# Cube_Motherboard.net
KiCad netlist of a schematic drawn in Altium Designer
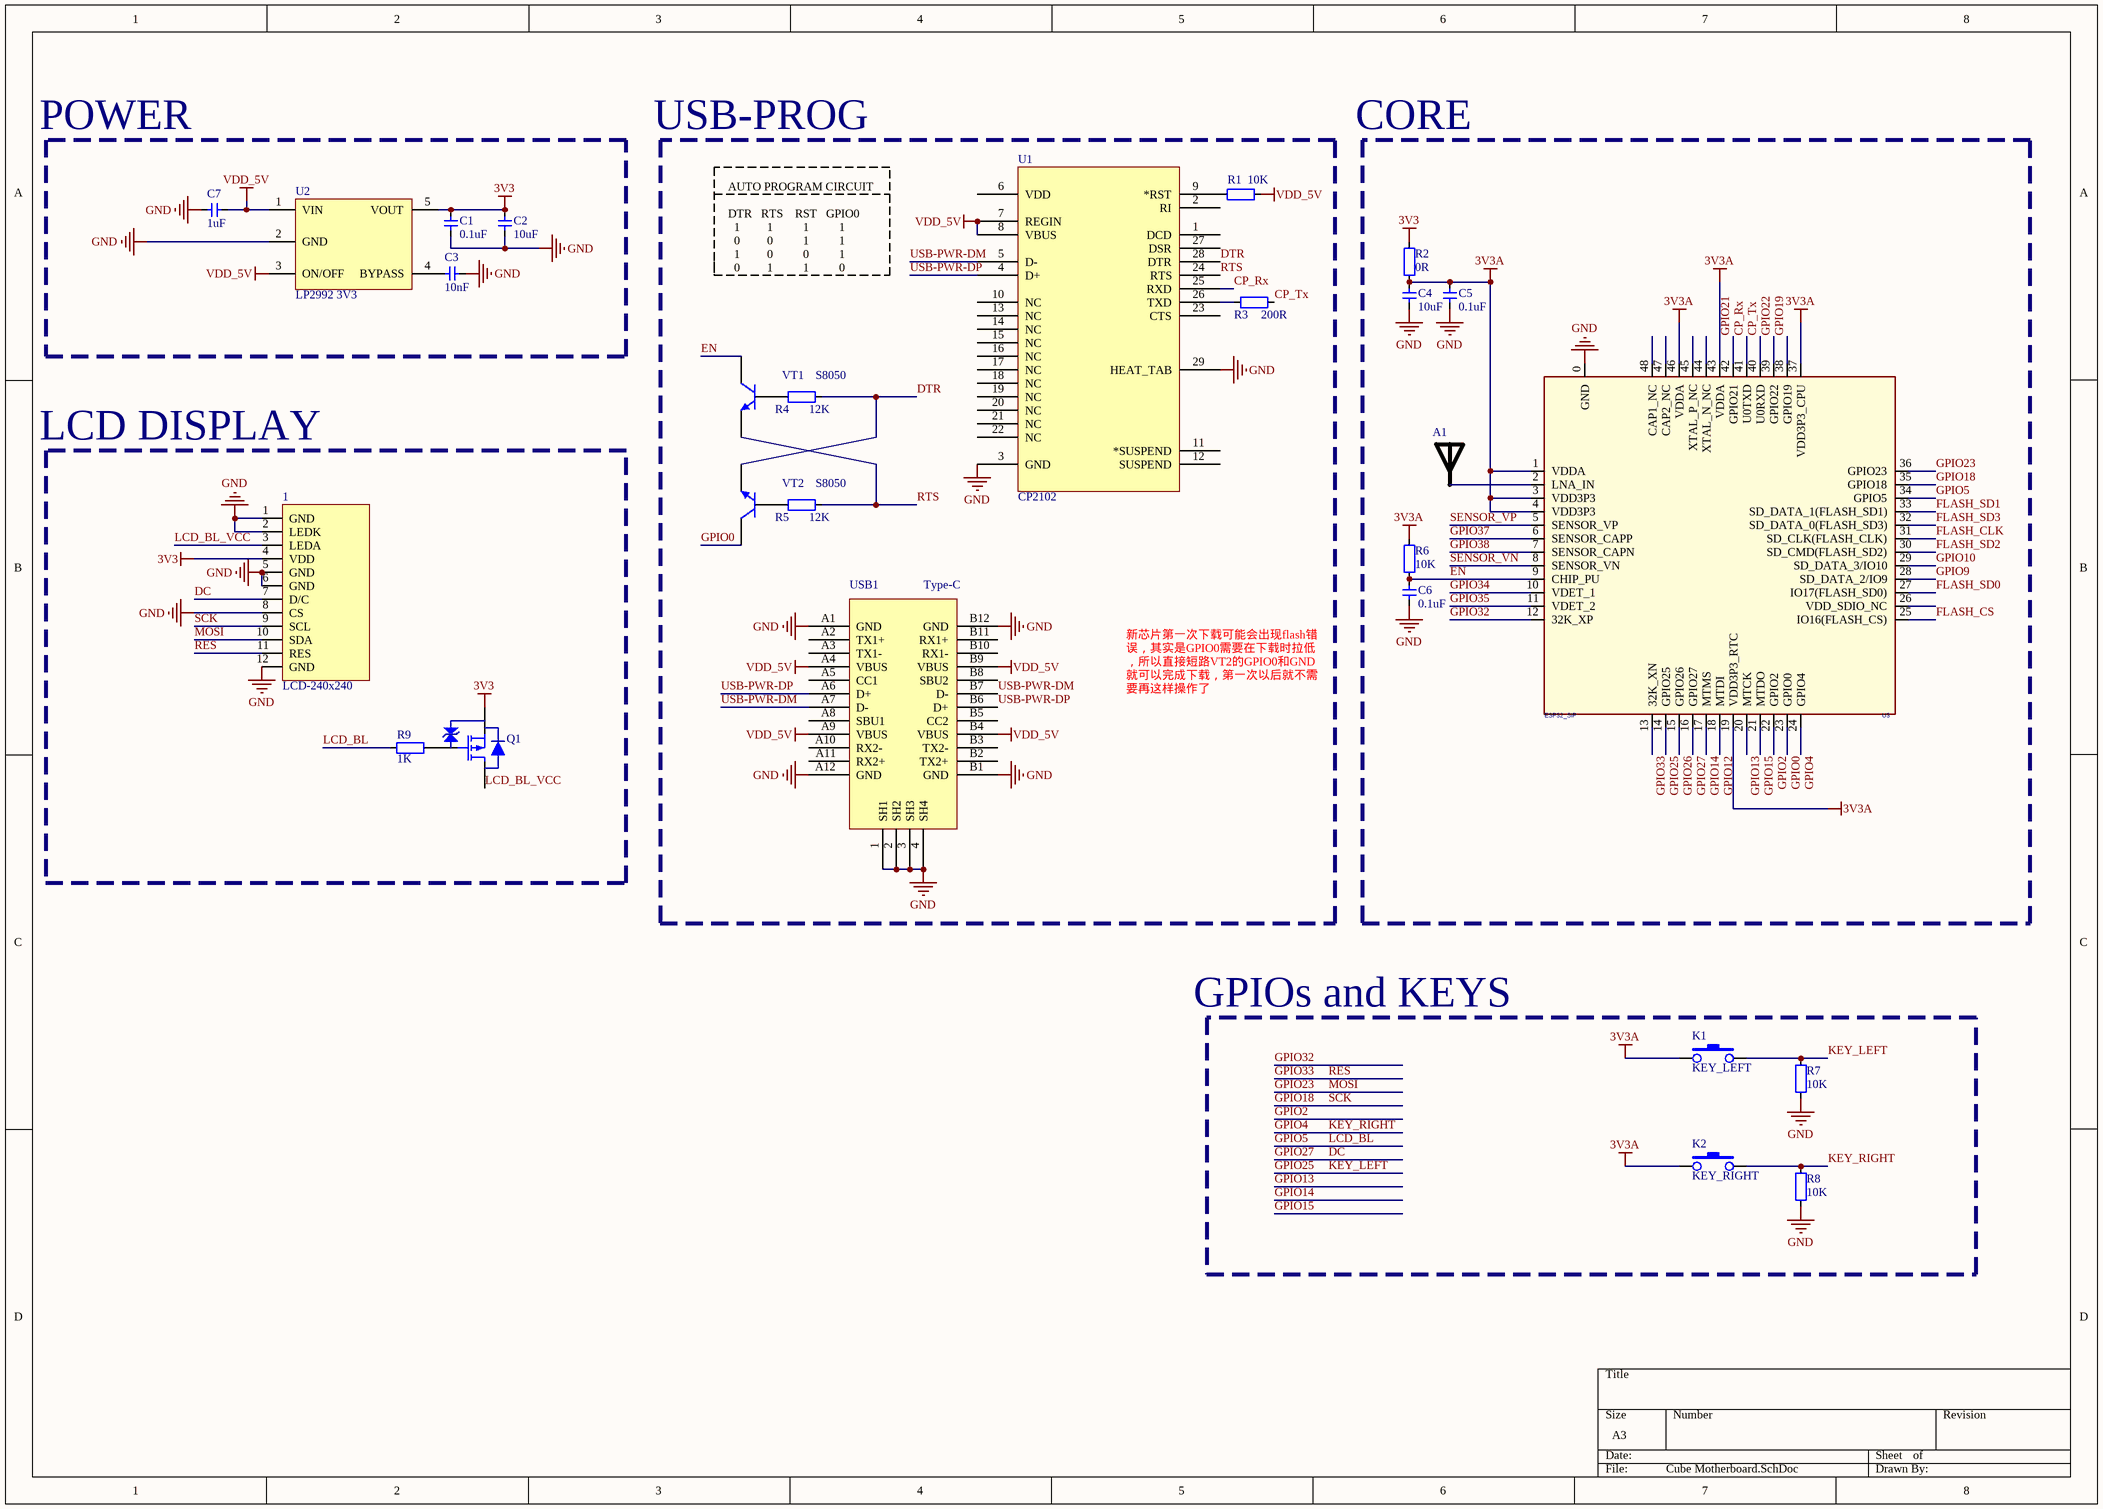
[diagram p0: Cube Motherboard.SchDoc]

(export (version "E")
  (design (tool "Eeschema 10.0.6"))
  (components
    (comp (ref "1")
      (value "LCD-240x240")
      (footprint "LCD-240X240-NOHOLE")
      (description "显示屏")
      (libsource (lib "mLib") (part "LCD-240x240"))
    )
    (comp (ref "A1")
      (value "RAINSUN")
      (footprint "ANT-Rainsun-AN5120")
      (libsource (lib "MyPcbLib") (part "ANT-Rainsun-AP5120"))
    )
    (comp (ref "C1")
      (value "0.1uF")
      (footprint "0603C")
      (description "Capacitor")
      (libsource (lib "MyPcbLib") (part "电容-0402"))
    )
    (comp (ref "C2")
      (value "10uF")
      (footprint "0603C")
      (description "Capacitor")
      (libsource (lib "MyPcbLib") (part "电容-0402"))
    )
    (comp (ref "C3")
      (value "10nF")
      (footprint "0603C")
      (description "Capacitor")
      (libsource (lib "MyPcbLib") (part "电容-0402"))
    )
    (comp (ref "C4")
      (value "10uF")
      (footprint "0603C")
      (description "Capacitor")
      (libsource (lib "MyPcbLib") (part "电容-0402"))
    )
    (comp (ref "C5")
      (value "0.1uF")
      (footprint "0603C")
      (description "Capacitor")
      (libsource (lib "MyPcbLib") (part "电容-0402"))
    )
    (comp (ref "C6")
      (value "0.1uF")
      (footprint "0603C")
      (description "Capacitor")
      (libsource (lib "MyPcbLib") (part "电容-0402"))
    )
    (comp (ref "C7")
      (value "1uF")
      (footprint "0603C")
      (description "Capacitor")
      (libsource (lib "MyPcbLib") (part "电容-0402"))
    )
    (comp (ref "K1") (value "KEY_LEFT") (footprint "SMD-SW2X4") (libsource (lib "轻触开关") (part "KEY")))
    (comp (ref "K2") (value "KEY_RIGHT") (footprint "SMD-SW2X4") (libsource (lib "轻触开关") (part "KEY")))
    (comp (ref "Q1")
      (value "AO3415A")
      (footprint "SOT23-3")
      (description "MOSFET")
      (fields (field (name "PUBLISHER") "Altium Limited"))
      (libsource (lib "MyPcbLib") (part "AO3415A"))
    )
    (comp (ref "R1")
      (value "10K")
      (footprint "0603R")
      (description "Resistor")
      (libsource (lib "") (part "电阻-0402_1"))
    )
    (comp (ref "R2")
      (value "0R")
      (footprint "0603R")
      (description "Resistor")
      (libsource (lib "MyPcbLib") (part "电阻-0402"))
    )
    (comp (ref "R3")
      (value "200R")
      (footprint "0603R")
      (description "Resistor")
      (libsource (lib "") (part "电阻-0402_1"))
    )
    (comp (ref "R4")
      (value "12K")
      (footprint "0603R")
      (description "Resistor")
      (libsource (lib "") (part "电阻-0402_1"))
    )
    (comp (ref "R5")
      (value "12K")
      (footprint "0603R")
      (description "Resistor")
      (libsource (lib "") (part "电阻-0402_1"))
    )
    (comp (ref "R6")
      (value "10K")
      (footprint "0603R")
      (description "Resistor")
      (libsource (lib "MyPcbLib") (part "电阻-0402"))
    )
    (comp (ref "R7")
      (value "10K")
      (footprint "0603R")
      (description "Resistor")
      (libsource (lib "MyPcbLib") (part "电阻-0402"))
    )
    (comp (ref "R8")
      (value "10K")
      (footprint "0603R")
      (description "Resistor")
      (libsource (lib "MyPcbLib") (part "电阻-0402"))
    )
    (comp (ref "R9")
      (value "1K")
      (footprint "0603R")
      (description "Resistor")
      (libsource (lib "") (part "电阻-0402_2"))
    )
    (comp (ref "U1")
      (value "CP2102")
      (footprint "QFN-28")
      (description "USB转TTL")
      (libsource (lib "mLib") (part "CP2102"))
    )
    (comp (ref "U2")
      (value "LP2992 3V3")
      (footprint "SOT23-5")
      (description "LDO")
      (libsource (lib "MyPcbLib") (part "LP2992"))
    )
    (comp (ref "U3")
      (value "ESP32_SIP")
      (footprint "QFN-48_7X7")
      (libsource (lib "MyPcbLib") (part "ESP32-PICO"))
    )
    (comp (ref "USB1")
      (value "Type-C")
      (footprint "Type-C-TOP")
      (libsource (lib "MyPcbLib") (part "USB-Type-C-TOP"))
    )
    (comp (ref "VT1")
      (value "S8050")
      (footprint "SMT_TRIODE_NPN")
      (description "Surface mount NPN transistor, package SOT-23")
      (libsource (lib "MyPcbLib") (part "SMT_TRIODE_NPN"))
    )
    (comp (ref "VT2")
      (value "S8050")
      (footprint "SMT_TRIODE_NPN")
      (description "Surface mount NPN transistor, package SOT-23")
      (libsource (lib "MyPcbLib") (part "SMT_TRIODE_NPN"))
    )
  )
  (nets
    (net (code "1") (name "/CP_Rx") (class "Default")
      (node (ref "U1") (pin "25") (pinfunction "RXD_25") (pintype "passive"))
      (node (ref "U3") (pin "41") (pinfunction "U0TXD_41") (pintype "power_in"))
    )
    (net (code "2") (name "/CP_Tx") (class "Default")
      (node (ref "R3") (pin "1") (pinfunction "1_1") (pintype "passive"))
      (node (ref "U3") (pin "40") (pinfunction "U0RXD_40") (pintype "power_in"))
    )
    (net (code "3") (name "/DC") (class "Default")
      (node (ref "1") (pin "7") (pinfunction "D/C_7") (pintype "passive"))
      (node (ref "U3") (pin "16") (pinfunction "GPIO27_16") (pintype "passive"))
    )
    (net (code "4") (name "/DTR") (class "Default")
      (node (ref "R4") (pin "1") (pinfunction "1_1") (pintype "passive"))
      (node (ref "U1") (pin "28") (pinfunction "DTR_28") (pintype "passive"))
      (node (ref "VT2") (pin "2") (pinfunction "E_2") (pintype "passive"))
    )
    (net (code "5") (name "/EN") (class "Default")
      (node (ref "C6") (pin "1") (pinfunction "1_1") (pintype "passive"))
      (node (ref "R6") (pin "2") (pinfunction "2_2") (pintype "passive"))
      (node (ref "U3") (pin "9") (pinfunction "CHIP_PU_9") (pintype "passive"))
      (node (ref "VT1") (pin "3") (pinfunction "C_3") (pintype "passive"))
    )
    (net (code "6") (name "/FLASH_CLK") (class "Default")
      (node (ref "U3") (pin "31") (pinfunction "SD_CLK(FLASH_CLK)_31") (pintype "passive"))
    )
    (net (code "7") (name "/FLASH_CS") (class "Default")
      (node (ref "U3") (pin "25") (pinfunction "IO16(FLASH_CS)_25") (pintype "passive"))
    )
    (net (code "8") (name "/FLASH_SD0") (class "Default")
      (node (ref "U3") (pin "27") (pinfunction "IO17(FLASH_SD0)_27") (pintype "passive"))
    )
    (net (code "9") (name "/FLASH_SD1") (class "Default")
      (node (ref "U3") (pin "33") (pinfunction "SD_DATA_1(FLASH_SD1)_33") (pintype "passive"))
    )
    (net (code "10") (name "/FLASH_SD2") (class "Default")
      (node (ref "U3") (pin "30") (pinfunction "SD_CMD(FLASH_SD2)_30") (pintype "passive"))
    )
    (net (code "11") (name "/FLASH_SD3") (class "Default")
      (node (ref "U3") (pin "32") (pinfunction "SD_DATA_0(FLASH_SD3)_32") (pintype "passive"))
    )
    (net (code "12") (name "/GPIO0") (class "Default")
      (node (ref "U3") (pin "23") (pinfunction "GPIO0_23") (pintype "passive"))
      (node (ref "VT2") (pin "3") (pinfunction "C_3") (pintype "passive"))
    )
    (net (code "13") (name "/GPIO2") (class "Default")
      (node (ref "U3") (pin "22") (pinfunction "GPIO2_22") (pintype "passive"))
    )
    (net (code "14") (name "/GPIO4") (class "Default")
      (node (ref "K2") (pin "3") (pinfunction "3_3") (pintype "passive"))
      (node (ref "R8") (pin "1") (pinfunction "1_1") (pintype "passive"))
      (node (ref "U3") (pin "24") (pinfunction "GPIO4_24") (pintype "passive"))
    )
    (net (code "15") (name "/GPIO5") (class "Default")
      (node (ref "R9") (pin "1") (pinfunction "1_1") (pintype "passive"))
      (node (ref "U3") (pin "34") (pinfunction "GPIO5_34") (pintype "passive"))
    )
    (net (code "16") (name "/GPIO9") (class "Default")
      (node (ref "U3") (pin "28") (pinfunction "SD_DATA_2/IO9_28") (pintype "passive"))
    )
    (net (code "17") (name "/GPIO10") (class "Default")
      (node (ref "U3") (pin "29") (pinfunction "SD_DATA_3/IO10_29") (pintype "passive"))
    )
    (net (code "18") (name "/GPIO12") (class "Default")
      (node (ref "U3") (pin "18") (pinfunction "MTDI_18") (pintype "passive"))
    )
    (net (code "19") (name "/GPIO13") (class "Default")
      (node (ref "U3") (pin "20") (pinfunction "MTCK_20") (pintype "passive"))
    )
    (net (code "20") (name "/GPIO14") (class "Default")
      (node (ref "U3") (pin "17") (pinfunction "MTMS_17") (pintype "passive"))
    )
    (net (code "21") (name "/GPIO15") (class "Default")
      (node (ref "U3") (pin "21") (pinfunction "MTDO_21") (pintype "passive"))
    )
    (net (code "22") (name "/GPIO18") (class "Default")
      (node (ref "1") (pin "9") (pinfunction "SCL_9") (pintype "passive"))
      (node (ref "U3") (pin "35") (pinfunction "GPIO18_35") (pintype "passive"))
    )
    (net (code "23") (name "/GPIO19") (class "Default")
      (node (ref "U3") (pin "38") (pinfunction "GPIO19_38") (pintype "passive"))
    )
    (net (code "24") (name "/GPIO21") (class "Default")
      (node (ref "U3") (pin "42") (pinfunction "GPIO21_42") (pintype "passive"))
    )
    (net (code "25") (name "/GPIO22") (class "Default")
      (node (ref "U3") (pin "39") (pinfunction "GPIO22_39") (pintype "passive"))
    )
    (net (code "26") (name "/GPIO23") (class "Default")
      (node (ref "1") (pin "10") (pinfunction "SDA_10") (pintype "passive"))
      (node (ref "U3") (pin "36") (pinfunction "GPIO23_36") (pintype "passive"))
    )
    (net (code "27") (name "/GPIO25") (class "Default")
      (node (ref "K1") (pin "3") (pinfunction "3_3") (pintype "passive"))
      (node (ref "R7") (pin "1") (pinfunction "1_1") (pintype "passive"))
      (node (ref "U3") (pin "14") (pinfunction "GPIO25_14") (pintype "passive"))
    )
    (net (code "28") (name "/GPIO26") (class "Default")
      (node (ref "U3") (pin "15") (pinfunction "GPIO26_15") (pintype "passive"))
    )
    (net (code "29") (name "/GPIO32") (class "Default")
      (node (ref "U3") (pin "12") (pinfunction "32K_XP_12") (pintype "passive"))
    )
    (net (code "30") (name "/GPIO33") (class "Default")
      (node (ref "1") (pin "11") (pinfunction "RES_11") (pintype "passive"))
      (node (ref "U3") (pin "13") (pinfunction "32K_XN_13") (pintype "passive"))
    )
    (net (code "31") (name "/GPIO34") (class "Default")
      (node (ref "U3") (pin "10") (pinfunction "VDET_1_10") (pintype "passive"))
    )
    (net (code "32") (name "/GPIO35") (class "Default")
      (node (ref "U3") (pin "11") (pinfunction "VDET_2_11") (pintype "passive"))
    )
    (net (code "33") (name "/GPIO37") (class "Default")
      (node (ref "U3") (pin "6") (pinfunction "SENSOR_CAPP_6") (pintype "passive"))
    )
    (net (code "34") (name "/GPIO38") (class "Default")
      (node (ref "U3") (pin "7") (pinfunction "SENSOR_CAPN_7") (pintype "passive"))
    )
    (net (code "35") (name "/LCD_BL_VCC") (class "Default")
      (node (ref "1") (pin "3") (pinfunction "LEDA_3") (pintype "passive"))
      (node (ref "Q1") (pin "3") (pinfunction "D_3") (pintype "passive"))
    )
    (net (code "36") (name "/RTS") (class "Default")
      (node (ref "R5") (pin "1") (pinfunction "1_1") (pintype "passive"))
      (node (ref "U1") (pin "24") (pinfunction "RTS_24") (pintype "passive"))
      (node (ref "VT1") (pin "2") (pinfunction "E_2") (pintype "passive"))
    )
    (net (code "37") (name "/SENSOR_VN") (class "Default")
      (node (ref "U3") (pin "8") (pinfunction "SENSOR_VN_8") (pintype "passive"))
    )
    (net (code "38") (name "/SENSOR_VP") (class "Default")
      (node (ref "U3") (pin "5") (pinfunction "SENSOR_VP_5") (pintype "passive"))
    )
    (net (code "39") (name "/USB-PWR-DM") (class "Default")
      (node (ref "U1") (pin "5") (pinfunction "D-_5") (pintype "passive"))
      (node (ref "USB1") (pin "A7") (pinfunction "D-_A7") (pintype "passive"))
      (node (ref "USB1") (pin "B7") (pinfunction "D-_B7") (pintype "passive"))
    )
    (net (code "40") (name "/USB-PWR-DP") (class "Default")
      (node (ref "U1") (pin "4") (pinfunction "D+_4") (pintype "passive"))
      (node (ref "USB1") (pin "A6") (pinfunction "D+_A6") (pintype "passive"))
      (node (ref "USB1") (pin "B6") (pinfunction "D+_B6") (pintype "passive"))
    )
    (net (code "41") (name "3V3") (class "Default")
      (node (ref "1") (pin "4") (pinfunction "VDD_4") (pintype "passive"))
      (node (ref "C1") (pin "2") (pinfunction "2_2") (pintype "passive"))
      (node (ref "C2") (pin "2") (pinfunction "2_2") (pintype "passive"))
      (node (ref "Q1") (pin "2") (pinfunction "S_2") (pintype "passive"))
      (node (ref "R2") (pin "1") (pinfunction "1_1") (pintype "passive"))
      (node (ref "U2") (pin "5") (pinfunction "VOUT_5") (pintype "passive"))
    )
    (net (code "42") (name "3V3A") (class "Default")
      (node (ref "C4") (pin "2") (pinfunction "2_2") (pintype "passive"))
      (node (ref "C5") (pin "2") (pinfunction "2_2") (pintype "passive"))
      (node (ref "K1") (pin "1") (pinfunction "1_1") (pintype "passive"))
      (node (ref "K2") (pin "1") (pinfunction "1_1") (pintype "passive"))
      (node (ref "R2") (pin "2") (pinfunction "2_2") (pintype "passive"))
      (node (ref "R6") (pin "1") (pinfunction "1_1") (pintype "passive"))
      (node (ref "U3") (pin "1") (pinfunction "VDDA_1") (pintype "power_in"))
      (node (ref "U3") (pin "19") (pinfunction "VDD3P3_RTC_19") (pintype "power_in"))
      (node (ref "U3") (pin "3") (pinfunction "VDD3P3_3") (pintype "power_in"))
      (node (ref "U3") (pin "37") (pinfunction "VDD3P3_CPU_37") (pintype "power_in"))
      (node (ref "U3") (pin "4") (pinfunction "VDD3P3_4") (pintype "power_in"))
      (node (ref "U3") (pin "43") (pinfunction "VDDA_43") (pintype "power_in"))
      (node (ref "U3") (pin "46") (pinfunction "VDDA_46") (pintype "power_in"))
    )
    (net (code "43") (name "GND") (class "Default")
      (node (ref "1") (pin "1") (pinfunction "GND_1") (pintype "passive"))
      (node (ref "1") (pin "12") (pinfunction "GND_12") (pintype "passive"))
      (node (ref "1") (pin "2") (pinfunction "LEDK_2") (pintype "passive"))
      (node (ref "1") (pin "5") (pinfunction "GND_5") (pintype "passive"))
      (node (ref "1") (pin "6") (pinfunction "GND_6") (pintype "passive"))
      (node (ref "1") (pin "8") (pinfunction "CS_8") (pintype "passive"))
      (node (ref "C1") (pin "1") (pinfunction "1_1") (pintype "passive"))
      (node (ref "C2") (pin "1") (pinfunction "1_1") (pintype "passive"))
      (node (ref "C3") (pin "1") (pinfunction "1_1") (pintype "passive"))
      (node (ref "C4") (pin "1") (pinfunction "1_1") (pintype "passive"))
      (node (ref "C5") (pin "1") (pinfunction "1_1") (pintype "passive"))
      (node (ref "C6") (pin "2") (pinfunction "2_2") (pintype "passive"))
      (node (ref "C7") (pin "2") (pinfunction "2_2") (pintype "passive"))
      (node (ref "R7") (pin "2") (pinfunction "2_2") (pintype "passive"))
      (node (ref "R8") (pin "2") (pinfunction "2_2") (pintype "passive"))
      (node (ref "U1") (pin "29") (pinfunction "HEAT_TAB_29") (pintype "passive"))
      (node (ref "U1") (pin "3") (pinfunction "GND_3") (pintype "passive"))
      (node (ref "U2") (pin "2") (pinfunction "GND_2") (pintype "passive"))
      (node (ref "U3") (pin "0") (pinfunction "GND_0") (pintype "power_in"))
      (node (ref "USB1") (pin "1") (pinfunction "SH1_1") (pintype "passive"))
      (node (ref "USB1") (pin "2") (pinfunction "SH2_2") (pintype "passive"))
      (node (ref "USB1") (pin "3") (pinfunction "SH3_3") (pintype "passive"))
      (node (ref "USB1") (pin "4") (pinfunction "SH4_4") (pintype "passive"))
      (node (ref "USB1") (pin "A1") (pinfunction "GND_A1") (pintype "passive"))
      (node (ref "USB1") (pin "A12") (pinfunction "GND_A12") (pintype "passive"))
      (node (ref "USB1") (pin "B1") (pinfunction "GND_B1") (pintype "passive"))
      (node (ref "USB1") (pin "B12") (pinfunction "GND_B12") (pintype "passive"))
    )
    (net (code "44") (name "Net-(Q1-G)") (class "Default")
      (node (ref "Q1") (pin "1") (pinfunction "G_1") (pintype "passive"))
      (node (ref "R9") (pin "2") (pinfunction "2_2") (pintype "passive"))
    )
    (net (code "45") (name "Net-(U1-*RST)") (class "Default")
      (node (ref "R1") (pin "2") (pinfunction "2_2") (pintype "passive"))
      (node (ref "U1") (pin "9") (pinfunction "*RST_9") (pintype "passive"))
    )
    (net (code "46") (name "Net-(U1-TXD)") (class "Default")
      (node (ref "R3") (pin "2") (pinfunction "2_2") (pintype "passive"))
      (node (ref "U1") (pin "26") (pinfunction "TXD_26") (pintype "passive"))
    )
    (net (code "47") (name "Net-(U2-BYPASS)") (class "Default")
      (node (ref "C3") (pin "2") (pinfunction "2_2") (pintype "passive"))
      (node (ref "U2") (pin "4") (pinfunction "BYPASS_4") (pintype "passive"))
    )
    (net (code "48") (name "Net-(U3-LNA_IN)") (class "Default")
      (node (ref "A1") (pin "1") (pinfunction "1_1") (pintype "passive"))
      (node (ref "U3") (pin "2") (pinfunction "LNA_IN_2") (pintype "passive"))
    )
    (net (code "49") (name "Net-(VT1-B)") (class "Default")
      (node (ref "R4") (pin "2") (pinfunction "2_2") (pintype "passive"))
      (node (ref "VT1") (pin "1") (pinfunction "B_1") (pintype "passive"))
    )
    (net (code "50") (name "Net-(VT2-B)") (class "Default")
      (node (ref "R5") (pin "2") (pinfunction "2_2") (pintype "passive"))
      (node (ref "VT2") (pin "1") (pinfunction "B_1") (pintype "passive"))
    )
    (net (code "51") (name "VDD_5V") (class "Default")
      (node (ref "C7") (pin "1") (pinfunction "1_1") (pintype "passive"))
      (node (ref "R1") (pin "1") (pinfunction "1_1") (pintype "passive"))
      (node (ref "U1") (pin "7") (pinfunction "REGIN_7") (pintype "passive"))
      (node (ref "U1") (pin "8") (pinfunction "VBUS_8") (pintype "passive"))
      (node (ref "U2") (pin "1") (pinfunction "VIN_1") (pintype "passive"))
      (node (ref "U2") (pin "3") (pinfunction "ON/OFF_3") (pintype "passive"))
      (node (ref "USB1") (pin "A4") (pinfunction "VBUS_A4") (pintype "passive"))
      (node (ref "USB1") (pin "A9") (pinfunction "VBUS_A9") (pintype "passive"))
      (node (ref "USB1") (pin "B4") (pinfunction "VBUS_B4") (pintype "passive"))
      (node (ref "USB1") (pin "B9") (pinfunction "VBUS_B9") (pintype "passive"))
    )
    (net (code "52") (name "unconnected-(U1-*SUSPEND-Pad11)") (class "Default")
      (node (ref "U1") (pin "11") (pinfunction "*SUSPEND_11") (pintype "passive"))
    )
    (net (code "53") (name "unconnected-(U1-CTS-Pad23)") (class "Default")
      (node (ref "U1") (pin "23") (pinfunction "CTS_23") (pintype "passive"))
    )
    (net (code "54") (name "unconnected-(U1-DCD-Pad1)") (class "Default")
      (node (ref "U1") (pin "1") (pinfunction "DCD_1") (pintype "passive"))
    )
    (net (code "55") (name "unconnected-(U1-DSR-Pad27)") (class "Default")
      (node (ref "U1") (pin "27") (pinfunction "DSR_27") (pintype "passive"))
    )
    (net (code "56") (name "unconnected-(U1-NC-Pad10)") (class "Default")
      (node (ref "U1") (pin "10") (pinfunction "NC_10") (pintype "passive"))
    )
    (net (code "57") (name "unconnected-(U1-NC-Pad13)") (class "Default")
      (node (ref "U1") (pin "13") (pinfunction "NC_13") (pintype "passive"))
    )
    (net (code "58") (name "unconnected-(U1-NC-Pad14)") (class "Default")
      (node (ref "U1") (pin "14") (pinfunction "NC_14") (pintype "passive"))
    )
    (net (code "59") (name "unconnected-(U1-NC-Pad15)") (class "Default")
      (node (ref "U1") (pin "15") (pinfunction "NC_15") (pintype "passive"))
    )
    (net (code "60") (name "unconnected-(U1-NC-Pad16)") (class "Default")
      (node (ref "U1") (pin "16") (pinfunction "NC_16") (pintype "passive"))
    )
    (net (code "61") (name "unconnected-(U1-NC-Pad17)") (class "Default")
      (node (ref "U1") (pin "17") (pinfunction "NC_17") (pintype "passive"))
    )
    (net (code "62") (name "unconnected-(U1-NC-Pad18)") (class "Default")
      (node (ref "U1") (pin "18") (pinfunction "NC_18") (pintype "passive"))
    )
    (net (code "63") (name "unconnected-(U1-NC-Pad19)") (class "Default")
      (node (ref "U1") (pin "19") (pinfunction "NC_19") (pintype "passive"))
    )
    (net (code "64") (name "unconnected-(U1-NC-Pad20)") (class "Default")
      (node (ref "U1") (pin "20") (pinfunction "NC_20") (pintype "passive"))
    )
    (net (code "65") (name "unconnected-(U1-NC-Pad21)") (class "Default")
      (node (ref "U1") (pin "21") (pinfunction "NC_21") (pintype "passive"))
    )
    (net (code "66") (name "unconnected-(U1-NC-Pad22)") (class "Default")
      (node (ref "U1") (pin "22") (pinfunction "NC_22") (pintype "passive"))
    )
    (net (code "67") (name "unconnected-(U1-RI-Pad2)") (class "Default")
      (node (ref "U1") (pin "2") (pinfunction "RI_2") (pintype "passive"))
    )
    (net (code "68") (name "unconnected-(U1-SUSPEND-Pad12)") (class "Default")
      (node (ref "U1") (pin "12") (pinfunction "SUSPEND_12") (pintype "passive"))
    )
    (net (code "69") (name "unconnected-(U1-VDD-Pad6)") (class "Default")
      (node (ref "U1") (pin "6") (pinfunction "VDD_6") (pintype "passive"))
    )
    (net (code "70") (name "unconnected-(U3-CAP1_NC-Pad48)") (class "Default")
      (node (ref "U3") (pin "48") (pinfunction "CAP1_NC_48") (pintype "passive"))
    )
    (net (code "71") (name "unconnected-(U3-CAP2_NC-Pad47)") (class "Default")
      (node (ref "U3") (pin "47") (pinfunction "CAP2_NC_47") (pintype "passive"))
    )
    (net (code "72") (name "unconnected-(U3-VDD_SDIO_NC-Pad26)") (class "Default")
      (node (ref "U3") (pin "26") (pinfunction "VDD_SDIO_NC_26") (pintype "passive"))
    )
    (net (code "73") (name "unconnected-(U3-XTAL_N_NC-Pad44)") (class "Default")
      (node (ref "U3") (pin "44") (pinfunction "XTAL_N_NC_44") (pintype "passive"))
    )
    (net (code "74") (name "unconnected-(U3-XTAL_P_NC-Pad45)") (class "Default")
      (node (ref "U3") (pin "45") (pinfunction "XTAL_P_NC_45") (pintype "passive"))
    )
    (net (code "75") (name "unconnected-(USB1-CC1-PadA5)") (class "Default")
      (node (ref "USB1") (pin "A5") (pinfunction "CC1_A5") (pintype "passive"))
    )
    (net (code "76") (name "unconnected-(USB1-CC2-PadB5)") (class "Default")
      (node (ref "USB1") (pin "B5") (pinfunction "CC2_B5") (pintype "passive"))
    )
    (net (code "77") (name "unconnected-(USB1-RX1+-PadB11)") (class "Default")
      (node (ref "USB1") (pin "B11") (pinfunction "RX1+_B11") (pintype "passive"))
    )
    (net (code "78") (name "unconnected-(USB1-RX1--PadB10)") (class "Default")
      (node (ref "USB1") (pin "B10") (pinfunction "RX1-_B10") (pintype "passive"))
    )
    (net (code "79") (name "unconnected-(USB1-RX2+-PadA11)") (class "Default")
      (node (ref "USB1") (pin "A11") (pinfunction "RX2+_A11") (pintype "passive"))
    )
    (net (code "80") (name "unconnected-(USB1-RX2--PadA10)") (class "Default")
      (node (ref "USB1") (pin "A10") (pinfunction "RX2-_A10") (pintype "passive"))
    )
    (net (code "81") (name "unconnected-(USB1-SBU1-PadA8)") (class "Default")
      (node (ref "USB1") (pin "A8") (pinfunction "SBU1_A8") (pintype "passive"))
    )
    (net (code "82") (name "unconnected-(USB1-SBU2-PadB8)") (class "Default")
      (node (ref "USB1") (pin "B8") (pinfunction "SBU2_B8") (pintype "passive"))
    )
    (net (code "83") (name "unconnected-(USB1-TX1+-PadA2)") (class "Default")
      (node (ref "USB1") (pin "A2") (pinfunction "TX1+_A2") (pintype "passive"))
    )
    (net (code "84") (name "unconnected-(USB1-TX1--PadA3)") (class "Default")
      (node (ref "USB1") (pin "A3") (pinfunction "TX1-_A3") (pintype "passive"))
    )
    (net (code "85") (name "unconnected-(USB1-TX2+-PadB2)") (class "Default")
      (node (ref "USB1") (pin "B2") (pinfunction "TX2+_B2") (pintype "passive"))
    )
    (net (code "86") (name "unconnected-(USB1-TX2--PadB3)") (class "Default")
      (node (ref "USB1") (pin "B3") (pinfunction "TX2-_B3") (pintype "passive"))
    )
  )
)
